# voice-card-controller-1_1-w-thru-hole-xt.net
KiCad netlist of a schematic drawn in EAGLE
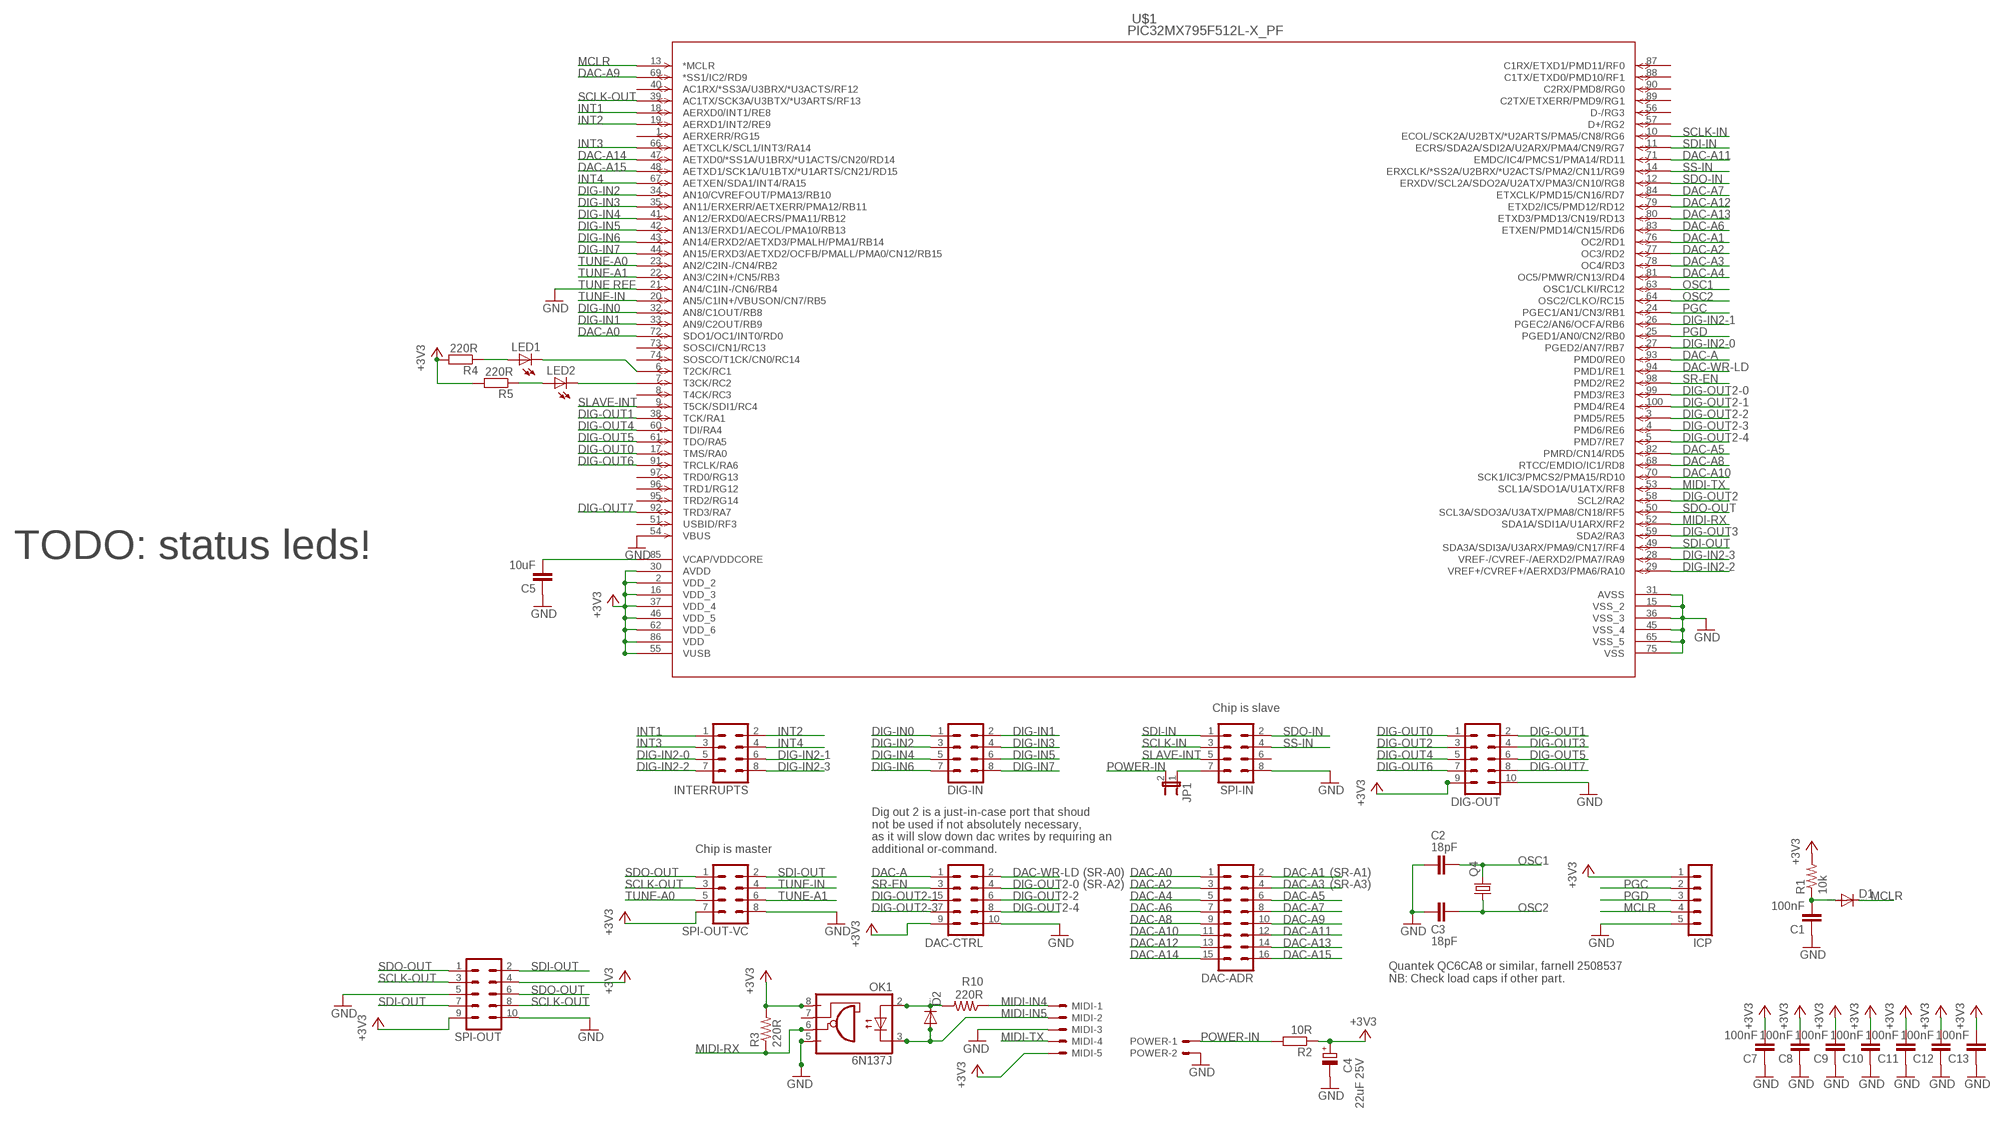
[diagram p0: schematic, sheet 1]

(export (version "E")
  (design (tool "Eeschema 10.0.6"))
  (components
    (comp (ref "C1")
      (value "100nF")
      (footprint "eagle-import:C0603")
      (libsource (lib "eagle-import") (part "C-EUC0603"))
    )
    (comp (ref "C2")
      (value "18pF")
      (footprint "eagle-import:C0603")
      (libsource (lib "eagle-import") (part "C-EUC0603"))
    )
    (comp (ref "C3")
      (value "18pF")
      (footprint "eagle-import:C0603")
      (libsource (lib "eagle-import") (part "C-EUC0603"))
    )
    (comp (ref "C4")
      (value "22uF 25V")
      (footprint "eagle-import:E2,5-5")
      (libsource (lib "eagle-import") (part "CPOL-EUE2.5-5"))
    )
    (comp (ref "C5")
      (value "10uF")
      (footprint "eagle-import:C0805")
      (libsource (lib "eagle-import") (part "C-EUC0805"))
    )
    (comp (ref "C7")
      (value "100nF")
      (footprint "eagle-import:C0603")
      (libsource (lib "eagle-import") (part "C-EUC0603"))
    )
    (comp (ref "C8")
      (value "100nF")
      (footprint "eagle-import:C0603")
      (libsource (lib "eagle-import") (part "C-EUC0603"))
    )
    (comp (ref "C9")
      (value "100nF")
      (footprint "eagle-import:C0603")
      (libsource (lib "eagle-import") (part "C-EUC0603"))
    )
    (comp (ref "C10")
      (value "100nF")
      (footprint "eagle-import:C0603")
      (libsource (lib "eagle-import") (part "C-EUC0603"))
    )
    (comp (ref "C11")
      (value "100nF")
      (footprint "eagle-import:C0603")
      (libsource (lib "eagle-import") (part "C-EUC0603"))
    )
    (comp (ref "C12")
      (value "100nF")
      (footprint "eagle-import:C0603")
      (libsource (lib "eagle-import") (part "C-EUC0603"))
    )
    (comp (ref "C13")
      (value "100nF")
      (footprint "eagle-import:C0603")
      (libsource (lib "eagle-import") (part "C-EUC0603"))
    )
    (comp (ref "D1")
      (value "DIODE-SOD80C")
      (footprint "eagle-import:SOD80C")
      (libsource (lib "eagle-import") (part "DIODE-SOD80C"))
    )
    (comp (ref "D2")
      (value "DIODE-SOD80C")
      (footprint "eagle-import:SOD80C")
      (libsource (lib "eagle-import") (part "DIODE-SOD80C"))
    )
    (comp (ref "DAC-ADR")
      (value "MA08-2J")
      (footprint "eagle-import:MA08-2J")
      (libsource (lib "eagle-import") (part "MA08-2J"))
    )
    (comp (ref "DAC-CTRL")
      (value "MA05-2J")
      (footprint "eagle-import:MA05-2J")
      (libsource (lib "eagle-import") (part "MA05-2J"))
    )
    (comp (ref "DIG-IN")
      (value "MA04-2J")
      (footprint "eagle-import:MA04-2J")
      (libsource (lib "eagle-import") (part "MA04-2J"))
    )
    (comp (ref "DIG-OUT")
      (value "MA05-2J")
      (footprint "eagle-import:MA05-2J")
      (libsource (lib "eagle-import") (part "MA05-2J"))
    )
    (comp (ref "ICP")
      (value "MA05-1")
      (footprint "eagle-import:MA05-1")
      (libsource (lib "eagle-import") (part "MA05-1"))
    )
    (comp (ref "INTERRUPTS")
      (value "MA04-2J")
      (footprint "eagle-import:MA04-2J")
      (libsource (lib "eagle-import") (part "MA04-2J"))
    )
    (comp (ref "JP1")
      (value "JP1E")
      (footprint "eagle-import:JP1")
      (libsource (lib "eagle-import") (part "JP1E"))
    )
    (comp (ref "LED1")
      (value "LEDCHIPLED_0603")
      (footprint "eagle-import:CHIPLED_0603")
      (libsource (lib "eagle-import") (part "LEDCHIPLED_0603"))
    )
    (comp (ref "LED2")
      (value "LEDCHIPLED_0603")
      (footprint "eagle-import:CHIPLED_0603")
      (libsource (lib "eagle-import") (part "LEDCHIPLED_0603"))
    )
    (comp (ref "MIDI")
      (value "22-23-2051")
      (footprint "eagle-import:22-23-2051")
      (fields (field (name "MF") "MOLEX"))
      (libsource (lib "eagle-import") (part "22-23-2051"))
    )
    (comp (ref "OK1")
      (value "6N137J")
      (footprint "eagle-import:DIL08-J")
      (libsource (lib "eagle-import") (part "6N137J"))
    )
    (comp (ref "POWER")
      (value "22-23-2021")
      (footprint "eagle-import:22-23-2021")
      (fields (field (name "MF") "MOLEX"))
      (libsource (lib "eagle-import") (part "22-23-2021"))
    )
    (comp (ref "Q4")
      (value "CRYSTALHC49S")
      (footprint "eagle-import:HC49_S")
      (libsource (lib "eagle-import") (part "CRYSTALHC49S"))
    )
    (comp (ref "R1")
      (value "10k")
      (footprint "eagle-import:R0805")
      (libsource (lib "eagle-import") (part "R-US_R0805"))
    )
    (comp (ref "R2")
      (value "10R")
      (footprint "eagle-import:0207_7")
      (libsource (lib "eagle-import") (part "R-EU_0207/7"))
    )
    (comp (ref "R3")
      (value "220R")
      (footprint "eagle-import:R0805")
      (libsource (lib "eagle-import") (part "R-US_R0805"))
    )
    (comp (ref "R4")
      (value "220R")
      (footprint "eagle-import:R0603")
      (libsource (lib "eagle-import") (part "R-EU_R0603"))
    )
    (comp (ref "R5")
      (value "220R")
      (footprint "eagle-import:R0603")
      (libsource (lib "eagle-import") (part "R-EU_R0603"))
    )
    (comp (ref "R10")
      (value "220R")
      (footprint "eagle-import:R0805")
      (libsource (lib "eagle-import") (part "R-US_R0805"))
    )
    (comp (ref "SPI-IN")
      (value "MA04-2J")
      (footprint "eagle-import:MA04-2J")
      (libsource (lib "eagle-import") (part "MA04-2J"))
    )
    (comp (ref "SPI-OUT")
      (value "MA05-2J")
      (footprint "eagle-import:MA05-2J")
      (libsource (lib "eagle-import") (part "MA05-2J"))
    )
    (comp (ref "SPI-OUT-VC")
      (value "MA04-2J")
      (footprint "eagle-import:MA04-2J")
      (libsource (lib "eagle-import") (part "MA04-2J"))
    )
    (comp (ref "U$1")
      (value "PIC32MX795F512L-X_PF")
      (footprint "eagle-import:TQFP100_14X14MC")
      (libsource (lib "eagle-import") (part "PIC32MX795F512L-X_PF"))
    )
  )
  (nets
    (net (code "1") (name "+3V3") (class "Default")
      (node (ref "C10") (pin "2") (pinfunction "2_2") (pintype "passive"))
      (node (ref "C11") (pin "2") (pinfunction "2_2") (pintype "passive"))
      (node (ref "C12") (pin "2") (pinfunction "2_2") (pintype "passive"))
      (node (ref "C13") (pin "2") (pinfunction "2_2") (pintype "passive"))
      (node (ref "C4") (pin "+") (pinfunction "+_+") (pintype "passive"))
      (node (ref "C7") (pin "2") (pinfunction "2_2") (pintype "passive"))
      (node (ref "C8") (pin "2") (pinfunction "2_2") (pintype "passive"))
      (node (ref "C9") (pin "2") (pinfunction "2_2") (pintype "passive"))
      (node (ref "DAC-CTRL") (pin "9") (pinfunction "9_9") (pintype "passive"))
      (node (ref "DIG-OUT") (pin "9") (pinfunction "9_9") (pintype "passive"))
      (node (ref "ICP") (pin "1") (pinfunction "1_1") (pintype "passive"))
      (node (ref "MIDI") (pin "5") (pinfunction "S_5") (pintype "passive"))
      (node (ref "OK1") (pin "8") (pinfunction "VCC_8") (pintype "passive"))
      (node (ref "R1") (pin "2") (pinfunction "2_2") (pintype "passive"))
      (node (ref "R2") (pin "1") (pinfunction "1_1") (pintype "passive"))
      (node (ref "R3") (pin "2") (pinfunction "2_2") (pintype "passive"))
      (node (ref "R4") (pin "2") (pinfunction "2_2") (pintype "passive"))
      (node (ref "R5") (pin "2") (pinfunction "2_2") (pintype "passive"))
      (node (ref "SPI-OUT") (pin "4") (pinfunction "4_4") (pintype "passive"))
      (node (ref "SPI-OUT") (pin "9") (pinfunction "9_9") (pintype "passive"))
      (node (ref "SPI-OUT-VC") (pin "7") (pinfunction "7_7") (pintype "passive"))
      (node (ref "U$1") (pin "16") (pinfunction "VDD_3_16") (pintype "power_in"))
      (node (ref "U$1") (pin "2") (pinfunction "VDD_2_2") (pintype "power_in"))
      (node (ref "U$1") (pin "30") (pinfunction "AVDD_30") (pintype "power_in"))
      (node (ref "U$1") (pin "37") (pinfunction "VDD_4_37") (pintype "power_in"))
      (node (ref "U$1") (pin "46") (pinfunction "VDD_5_46") (pintype "power_in"))
      (node (ref "U$1") (pin "55") (pinfunction "VUSB_55") (pintype "power_in"))
      (node (ref "U$1") (pin "62") (pinfunction "VDD_6_62") (pintype "power_in"))
      (node (ref "U$1") (pin "86") (pinfunction "VDD_86") (pintype "power_in"))
    )
    (net (code "2") (name "/DAC-A") (class "Default")
      (node (ref "DAC-CTRL") (pin "1") (pinfunction "1_1") (pintype "passive"))
      (node (ref "U$1") (pin "93") (pinfunction "PMD0/RE0_93") (pintype "bidirectional"))
    )
    (net (code "3") (name "/DAC-A0") (class "Default")
      (node (ref "DAC-ADR") (pin "1") (pinfunction "1_1") (pintype "passive"))
      (node (ref "U$1") (pin "72") (pinfunction "SDO1/OC1/INT0/RD0_72") (pintype "bidirectional"))
    )
    (net (code "4") (name "/DAC-A1") (class "Default")
      (node (ref "DAC-ADR") (pin "2") (pinfunction "2_2") (pintype "passive"))
      (node (ref "U$1") (pin "76") (pinfunction "OC2/RD1_76") (pintype "bidirectional"))
    )
    (net (code "5") (name "/DAC-A2") (class "Default")
      (node (ref "DAC-ADR") (pin "3") (pinfunction "3_3") (pintype "passive"))
      (node (ref "U$1") (pin "77") (pinfunction "OC3/RD2_77") (pintype "bidirectional"))
    )
    (net (code "6") (name "/DAC-A3") (class "Default")
      (node (ref "DAC-ADR") (pin "4") (pinfunction "4_4") (pintype "passive"))
      (node (ref "U$1") (pin "78") (pinfunction "OC4/RD3_78") (pintype "bidirectional"))
    )
    (net (code "7") (name "/DAC-A4") (class "Default")
      (node (ref "DAC-ADR") (pin "5") (pinfunction "5_5") (pintype "passive"))
      (node (ref "U$1") (pin "81") (pinfunction "OC5/PMWR/CN13/RD4_81") (pintype "bidirectional"))
    )
    (net (code "8") (name "/DAC-A5") (class "Default")
      (node (ref "DAC-ADR") (pin "6") (pinfunction "6_6") (pintype "passive"))
      (node (ref "U$1") (pin "82") (pinfunction "PMRD/CN14/RD5_82") (pintype "bidirectional"))
    )
    (net (code "9") (name "/DAC-A6") (class "Default")
      (node (ref "DAC-ADR") (pin "7") (pinfunction "7_7") (pintype "passive"))
      (node (ref "U$1") (pin "83") (pinfunction "ETXEN/PMD14/CN15/RD6_83") (pintype "bidirectional"))
    )
    (net (code "10") (name "/DAC-A7") (class "Default")
      (node (ref "DAC-ADR") (pin "8") (pinfunction "8_8") (pintype "passive"))
      (node (ref "U$1") (pin "84") (pinfunction "ETXCLK/PMD15/CN16/RD7_84") (pintype "bidirectional"))
    )
    (net (code "11") (name "/DAC-A8") (class "Default")
      (node (ref "DAC-ADR") (pin "9") (pinfunction "9_9") (pintype "passive"))
      (node (ref "U$1") (pin "68") (pinfunction "RTCC/EMDIO/IC1/RD8_68") (pintype "bidirectional"))
    )
    (net (code "12") (name "/DAC-A9") (class "Default")
      (node (ref "DAC-ADR") (pin "10") (pinfunction "10_10") (pintype "passive"))
      (node (ref "U$1") (pin "69") (pinfunction "*SS1/IC2/RD9_69") (pintype "bidirectional"))
    )
    (net (code "13") (name "/DAC-A10") (class "Default")
      (node (ref "DAC-ADR") (pin "11") (pinfunction "11_11") (pintype "passive"))
      (node (ref "U$1") (pin "70") (pinfunction "SCK1/IC3/PMCS2/PMA15/RD10_70") (pintype "bidirectional"))
    )
    (net (code "14") (name "/DAC-A11") (class "Default")
      (node (ref "DAC-ADR") (pin "12") (pinfunction "12_12") (pintype "passive"))
      (node (ref "U$1") (pin "71") (pinfunction "EMDC/IC4/PMCS1/PMA14/RD11_71") (pintype "bidirectional"))
    )
    (net (code "15") (name "/DAC-A12") (class "Default")
      (node (ref "DAC-ADR") (pin "13") (pinfunction "13_13") (pintype "passive"))
      (node (ref "U$1") (pin "79") (pinfunction "ETXD2/IC5/PMD12/RD12_79") (pintype "bidirectional"))
    )
    (net (code "16") (name "/DAC-A13") (class "Default")
      (node (ref "DAC-ADR") (pin "14") (pinfunction "14_14") (pintype "passive"))
      (node (ref "U$1") (pin "80") (pinfunction "ETXD3/PMD13/CN19/RD13_80") (pintype "bidirectional"))
    )
    (net (code "17") (name "/DAC-A14") (class "Default")
      (node (ref "DAC-ADR") (pin "15") (pinfunction "15_15") (pintype "passive"))
      (node (ref "U$1") (pin "47") (pinfunction "AETXD0/*SS1A/U1BRX/*U1ACTS/CN20/RD14_47") (pintype "bidirectional"))
    )
    (net (code "18") (name "/DAC-A15") (class "Default")
      (node (ref "DAC-ADR") (pin "16") (pinfunction "16_16") (pintype "passive"))
      (node (ref "U$1") (pin "48") (pinfunction "AETXD1/SCK1A/U1BTX/*U1ARTS/CN21/RD15_48") (pintype "bidirectional"))
    )
    (net (code "19") (name "/DAC-WR-LD") (class "Default")
      (node (ref "DAC-CTRL") (pin "2") (pinfunction "2_2") (pintype "passive"))
      (node (ref "U$1") (pin "94") (pinfunction "PMD1/RE1_94") (pintype "bidirectional"))
    )
    (net (code "20") (name "/DIG-IN0") (class "Default")
      (node (ref "DIG-IN") (pin "1") (pinfunction "1_1") (pintype "passive"))
      (node (ref "U$1") (pin "32") (pinfunction "AN8/C1OUT/RB8_32") (pintype "bidirectional"))
    )
    (net (code "21") (name "/DIG-IN1") (class "Default")
      (node (ref "DIG-IN") (pin "2") (pinfunction "2_2") (pintype "passive"))
      (node (ref "U$1") (pin "33") (pinfunction "AN9/C2OUT/RB9_33") (pintype "bidirectional"))
    )
    (net (code "22") (name "/DIG-IN2") (class "Default")
      (node (ref "DIG-IN") (pin "3") (pinfunction "3_3") (pintype "passive"))
      (node (ref "U$1") (pin "34") (pinfunction "AN10/CVREFOUT/PMA13/RB10_34") (pintype "bidirectional"))
    )
    (net (code "23") (name "/DIG-IN2-0") (class "Default")
      (node (ref "INTERRUPTS") (pin "5") (pinfunction "5_5") (pintype "passive"))
      (node (ref "U$1") (pin "27") (pinfunction "PGED2/AN7/RB7_27") (pintype "bidirectional"))
    )
    (net (code "24") (name "/DIG-IN2-1") (class "Default")
      (node (ref "INTERRUPTS") (pin "6") (pinfunction "6_6") (pintype "passive"))
      (node (ref "U$1") (pin "26") (pinfunction "PGEC2/AN6/OCFA/RB6_26") (pintype "bidirectional"))
    )
    (net (code "25") (name "/DIG-IN2-2") (class "Default")
      (node (ref "INTERRUPTS") (pin "7") (pinfunction "7_7") (pintype "passive"))
      (node (ref "U$1") (pin "29") (pinfunction "VREF+/CVREF+/AERXD3/PMA6/RA10_29") (pintype "bidirectional"))
    )
    (net (code "26") (name "/DIG-IN2-3") (class "Default")
      (node (ref "INTERRUPTS") (pin "8") (pinfunction "8_8") (pintype "passive"))
      (node (ref "U$1") (pin "28") (pinfunction "VREF-/CVREF-/AERXD2/PMA7/RA9_28") (pintype "bidirectional"))
    )
    (net (code "27") (name "/DIG-IN3") (class "Default")
      (node (ref "DIG-IN") (pin "4") (pinfunction "4_4") (pintype "passive"))
      (node (ref "U$1") (pin "35") (pinfunction "AN11/ERXERR/AETXERR/PMA12/RB11_35") (pintype "bidirectional"))
    )
    (net (code "28") (name "/DIG-IN4") (class "Default")
      (node (ref "DIG-IN") (pin "5") (pinfunction "5_5") (pintype "passive"))
      (node (ref "U$1") (pin "41") (pinfunction "AN12/ERXD0/AECRS/PMA11/RB12_41") (pintype "bidirectional"))
    )
    (net (code "29") (name "/DIG-IN5") (class "Default")
      (node (ref "DIG-IN") (pin "6") (pinfunction "6_6") (pintype "passive"))
      (node (ref "U$1") (pin "42") (pinfunction "AN13/ERXD1/AECOL/PMA10/RB13_42") (pintype "bidirectional"))
    )
    (net (code "30") (name "/DIG-IN6") (class "Default")
      (node (ref "DIG-IN") (pin "7") (pinfunction "7_7") (pintype "passive"))
      (node (ref "U$1") (pin "43") (pinfunction "AN14/ERXD2/AETXD3/PMALH/PMA1/RB14_43") (pintype "bidirectional"))
    )
    (net (code "31") (name "/DIG-IN7") (class "Default")
      (node (ref "DIG-IN") (pin "8") (pinfunction "8_8") (pintype "passive"))
      (node (ref "U$1") (pin "44") (pinfunction "AN15/ERXD3/AETXD2/OCFB/PMALL/PMA0/CN12/RB15_44") (pintype "bidirectional"))
    )
    (net (code "32") (name "/DIG-OUT0") (class "Default")
      (node (ref "DIG-OUT") (pin "1") (pinfunction "1_1") (pintype "passive"))
      (node (ref "U$1") (pin "17") (pinfunction "TMS/RA0_17") (pintype "bidirectional"))
    )
    (net (code "33") (name "/DIG-OUT1") (class "Default")
      (node (ref "DIG-OUT") (pin "2") (pinfunction "2_2") (pintype "passive"))
      (node (ref "U$1") (pin "38") (pinfunction "TCK/RA1_38") (pintype "bidirectional"))
    )
    (net (code "34") (name "/DIG-OUT2") (class "Default")
      (node (ref "DIG-OUT") (pin "3") (pinfunction "3_3") (pintype "passive"))
      (node (ref "U$1") (pin "58") (pinfunction "SCL2/RA2_58") (pintype "bidirectional"))
    )
    (net (code "35") (name "/DIG-OUT2-0") (class "Default")
      (node (ref "DAC-CTRL") (pin "4") (pinfunction "4_4") (pintype "passive"))
      (node (ref "U$1") (pin "99") (pinfunction "PMD3/RE3_99") (pintype "bidirectional"))
    )
    (net (code "36") (name "/DIG-OUT2-1") (class "Default")
      (node (ref "DAC-CTRL") (pin "5") (pinfunction "5_5") (pintype "passive"))
      (node (ref "U$1") (pin "100") (pinfunction "PMD4/RE4_100") (pintype "bidirectional"))
    )
    (net (code "37") (name "/DIG-OUT2-2") (class "Default")
      (node (ref "DAC-CTRL") (pin "6") (pinfunction "6_6") (pintype "passive"))
      (node (ref "U$1") (pin "3") (pinfunction "PMD5/RE5_3") (pintype "bidirectional"))
    )
    (net (code "38") (name "/DIG-OUT2-3") (class "Default")
      (node (ref "DAC-CTRL") (pin "7") (pinfunction "7_7") (pintype "passive"))
      (node (ref "U$1") (pin "4") (pinfunction "PMD6/RE6_4") (pintype "bidirectional"))
    )
    (net (code "39") (name "/DIG-OUT2-4") (class "Default")
      (node (ref "DAC-CTRL") (pin "8") (pinfunction "8_8") (pintype "passive"))
      (node (ref "U$1") (pin "5") (pinfunction "PMD7/RE7_5") (pintype "bidirectional"))
    )
    (net (code "40") (name "/DIG-OUT3") (class "Default")
      (node (ref "DIG-OUT") (pin "4") (pinfunction "4_4") (pintype "passive"))
      (node (ref "U$1") (pin "59") (pinfunction "SDA2/RA3_59") (pintype "bidirectional"))
    )
    (net (code "41") (name "/DIG-OUT4") (class "Default")
      (node (ref "DIG-OUT") (pin "5") (pinfunction "5_5") (pintype "passive"))
      (node (ref "U$1") (pin "60") (pinfunction "TDI/RA4_60") (pintype "bidirectional"))
    )
    (net (code "42") (name "/DIG-OUT5") (class "Default")
      (node (ref "DIG-OUT") (pin "6") (pinfunction "6_6") (pintype "passive"))
      (node (ref "U$1") (pin "61") (pinfunction "TDO/RA5_61") (pintype "bidirectional"))
    )
    (net (code "43") (name "/DIG-OUT6") (class "Default")
      (node (ref "DIG-OUT") (pin "7") (pinfunction "7_7") (pintype "passive"))
      (node (ref "U$1") (pin "91") (pinfunction "TRCLK/RA6_91") (pintype "bidirectional"))
    )
    (net (code "44") (name "/DIG-OUT7") (class "Default")
      (node (ref "DIG-OUT") (pin "8") (pinfunction "8_8") (pintype "passive"))
      (node (ref "U$1") (pin "92") (pinfunction "TRD3/RA7_92") (pintype "bidirectional"))
    )
    (net (code "45") (name "/INT1") (class "Default")
      (node (ref "INTERRUPTS") (pin "1") (pinfunction "1_1") (pintype "passive"))
      (node (ref "U$1") (pin "18") (pinfunction "AERXD0/INT1/RE8_18") (pintype "bidirectional"))
    )
    (net (code "46") (name "/INT2") (class "Default")
      (node (ref "INTERRUPTS") (pin "2") (pinfunction "2_2") (pintype "passive"))
      (node (ref "U$1") (pin "19") (pinfunction "AERXD1/INT2/RE9_19") (pintype "bidirectional"))
    )
    (net (code "47") (name "/INT3") (class "Default")
      (node (ref "INTERRUPTS") (pin "3") (pinfunction "3_3") (pintype "passive"))
      (node (ref "U$1") (pin "66") (pinfunction "AETXCLK/SCL1/INT3/RA14_66") (pintype "bidirectional"))
    )
    (net (code "48") (name "/INT4") (class "Default")
      (node (ref "INTERRUPTS") (pin "4") (pinfunction "4_4") (pintype "passive"))
      (node (ref "U$1") (pin "67") (pinfunction "AETXEN/SDA1/INT4/RA15_67") (pintype "bidirectional"))
    )
    (net (code "49") (name "/MCLR") (class "Default")
      (node (ref "D1") (pin "C") (pinfunction "C_C") (pintype "passive"))
      (node (ref "ICP") (pin "4") (pinfunction "4_4") (pintype "passive"))
      (node (ref "U$1") (pin "13") (pinfunction "*MCLR_13") (pintype "input"))
    )
    (net (code "50") (name "/MIDI-IN4") (class "Default")
      (node (ref "MIDI") (pin "1") (pinfunction "S_1") (pintype "passive"))
      (node (ref "R10") (pin "1") (pinfunction "1_1") (pintype "passive"))
    )
    (net (code "51") (name "/MIDI-IN5") (class "Default")
      (node (ref "D2") (pin "A") (pinfunction "A_A") (pintype "passive"))
      (node (ref "MIDI") (pin "2") (pinfunction "S_2") (pintype "passive"))
      (node (ref "OK1") (pin "3") (pinfunction "C_3") (pintype "passive"))
    )
    (net (code "52") (name "/MIDI-RX") (class "Default")
      (node (ref "OK1") (pin "6") (pinfunction "VO_6") (pintype "passive"))
      (node (ref "R3") (pin "1") (pinfunction "1_1") (pintype "passive"))
      (node (ref "U$1") (pin "52") (pinfunction "SDA1A/SDI1A/U1ARX/RF2_52") (pintype "bidirectional"))
    )
    (net (code "53") (name "/MIDI-TX") (class "Default")
      (node (ref "MIDI") (pin "4") (pinfunction "S_4") (pintype "passive"))
      (node (ref "U$1") (pin "53") (pinfunction "SCL1A/SDO1A/U1ATX/RF8_53") (pintype "bidirectional"))
    )
    (net (code "54") (name "/OSC1") (class "Default")
      (node (ref "C2") (pin "1") (pinfunction "1_1") (pintype "passive"))
      (node (ref "Q4") (pin "2") (pinfunction "2_2") (pintype "passive"))
      (node (ref "U$1") (pin "63") (pinfunction "OSC1/CLKI/RC12_63") (pintype "bidirectional"))
    )
    (net (code "55") (name "/OSC2") (class "Default")
      (node (ref "C3") (pin "1") (pinfunction "1_1") (pintype "passive"))
      (node (ref "Q4") (pin "1") (pinfunction "1_1") (pintype "passive"))
      (node (ref "U$1") (pin "64") (pinfunction "OSC2/CLKO/RC15_64") (pintype "bidirectional"))
    )
    (net (code "56") (name "/PGC") (class "Default")
      (node (ref "ICP") (pin "2") (pinfunction "2_2") (pintype "passive"))
      (node (ref "U$1") (pin "24") (pinfunction "PGEC1/AN1/CN3/RB1_24") (pintype "bidirectional"))
    )
    (net (code "57") (name "/PGD") (class "Default")
      (node (ref "ICP") (pin "3") (pinfunction "3_3") (pintype "passive"))
      (node (ref "U$1") (pin "25") (pinfunction "PGED1/AN0/CN2/RB0_25") (pintype "bidirectional"))
    )
    (net (code "58") (name "/POWER-IN") (class "Default")
      (node (ref "JP1") (pin "2") (pinfunction "2_2") (pintype "passive"))
      (node (ref "POWER") (pin "1") (pinfunction "S_1") (pintype "passive"))
      (node (ref "R2") (pin "2") (pinfunction "2_2") (pintype "passive"))
    )
    (net (code "59") (name "/SCLK-IN") (class "Default")
      (node (ref "SPI-IN") (pin "3") (pinfunction "3_3") (pintype "passive"))
      (node (ref "U$1") (pin "10") (pinfunction "ECOL/SCK2A/U2BTX/*U2ARTS/PMA5/CN8/RG6_10") (pintype "bidirectional"))
    )
    (net (code "60") (name "/SCLK-OUT") (class "Default")
      (node (ref "SPI-OUT") (pin "3") (pinfunction "3_3") (pintype "passive"))
      (node (ref "SPI-OUT") (pin "8") (pinfunction "8_8") (pintype "passive"))
      (node (ref "SPI-OUT-VC") (pin "3") (pinfunction "3_3") (pintype "passive"))
      (node (ref "U$1") (pin "39") (pinfunction "AC1TX/SCK3A/U3BTX/*U3ARTS/RF13_39") (pintype "bidirectional"))
    )
    (net (code "61") (name "/SDI-IN") (class "Default")
      (node (ref "SPI-IN") (pin "1") (pinfunction "1_1") (pintype "passive"))
      (node (ref "U$1") (pin "11") (pinfunction "ECRS/SDA2A/SDI2A/U2ARX/PMA4/CN9/RG7_11") (pintype "bidirectional"))
    )
    (net (code "62") (name "/SDI-OUT") (class "Default")
      (node (ref "SPI-OUT") (pin "2") (pinfunction "2_2") (pintype "passive"))
      (node (ref "SPI-OUT") (pin "7") (pinfunction "7_7") (pintype "passive"))
      (node (ref "SPI-OUT-VC") (pin "2") (pinfunction "2_2") (pintype "passive"))
      (node (ref "U$1") (pin "49") (pinfunction "SDA3A/SDI3A/U3ARX/PMA9/CN17/RF4_49") (pintype "bidirectional"))
    )
    (net (code "63") (name "/SDO-IN") (class "Default")
      (node (ref "SPI-IN") (pin "2") (pinfunction "2_2") (pintype "passive"))
      (node (ref "U$1") (pin "12") (pinfunction "ERXDV/SCL2A/SDO2A/U2ATX/PMA3/CN10/RG8_12") (pintype "bidirectional"))
    )
    (net (code "64") (name "/SDO-OUT") (class "Default")
      (node (ref "SPI-OUT") (pin "1") (pinfunction "1_1") (pintype "passive"))
      (node (ref "SPI-OUT") (pin "6") (pinfunction "6_6") (pintype "passive"))
      (node (ref "SPI-OUT-VC") (pin "1") (pinfunction "1_1") (pintype "passive"))
      (node (ref "U$1") (pin "50") (pinfunction "SCL3A/SDO3A/U3ATX/PMA8/CN18/RF5_50") (pintype "bidirectional"))
    )
    (net (code "65") (name "/SLAVE-INT") (class "Default")
      (node (ref "SPI-IN") (pin "5") (pinfunction "5_5") (pintype "passive"))
      (node (ref "U$1") (pin "9") (pinfunction "T5CK/SDI1/RC4_9") (pintype "bidirectional"))
    )
    (net (code "66") (name "/SR-EN") (class "Default")
      (node (ref "DAC-CTRL") (pin "3") (pinfunction "3_3") (pintype "passive"))
      (node (ref "U$1") (pin "98") (pinfunction "PMD2/RE2_98") (pintype "bidirectional"))
    )
    (net (code "67") (name "/SS-IN") (class "Default")
      (node (ref "SPI-IN") (pin "4") (pinfunction "4_4") (pintype "passive"))
      (node (ref "U$1") (pin "14") (pinfunction "ERXCLK/*SS2A/U2BRX/*U2ACTS/PMA2/CN11/RG9_14") (pintype "bidirectional"))
    )
    (net (code "68") (name "/TUNE-A0") (class "Default")
      (node (ref "SPI-OUT-VC") (pin "5") (pinfunction "5_5") (pintype "passive"))
      (node (ref "U$1") (pin "23") (pinfunction "AN2/C2IN-/CN4/RB2_23") (pintype "bidirectional"))
    )
    (net (code "69") (name "/TUNE-A1") (class "Default")
      (node (ref "SPI-OUT-VC") (pin "6") (pinfunction "6_6") (pintype "passive"))
      (node (ref "U$1") (pin "22") (pinfunction "AN3/C2IN+/CN5/RB3_22") (pintype "bidirectional"))
    )
    (net (code "70") (name "/TUNE-IN") (class "Default")
      (node (ref "SPI-OUT-VC") (pin "4") (pinfunction "4_4") (pintype "passive"))
      (node (ref "U$1") (pin "20") (pinfunction "AN5/C1IN+/VBUSON/CN7/RB5_20") (pintype "bidirectional"))
    )
    (net (code "71") (name "GND") (class "Default")
      (node (ref "C1") (pin "1") (pinfunction "1_1") (pintype "passive"))
      (node (ref "C10") (pin "1") (pinfunction "1_1") (pintype "passive"))
      (node (ref "C11") (pin "1") (pinfunction "1_1") (pintype "passive"))
      (node (ref "C12") (pin "1") (pinfunction "1_1") (pintype "passive"))
      (node (ref "C13") (pin "1") (pinfunction "1_1") (pintype "passive"))
      (node (ref "C2") (pin "2") (pinfunction "2_2") (pintype "passive"))
      (node (ref "C3") (pin "2") (pinfunction "2_2") (pintype "passive"))
      (node (ref "C4") (pin "-") (pinfunction "-_-") (pintype "passive"))
      (node (ref "C5") (pin "1") (pinfunction "1_1") (pintype "passive"))
      (node (ref "C7") (pin "1") (pinfunction "1_1") (pintype "passive"))
      (node (ref "C8") (pin "1") (pinfunction "1_1") (pintype "passive"))
      (node (ref "C9") (pin "1") (pinfunction "1_1") (pintype "passive"))
      (node (ref "DAC-CTRL") (pin "10") (pinfunction "10_10") (pintype "passive"))
      (node (ref "DIG-OUT") (pin "10") (pinfunction "10_10") (pintype "passive"))
      (node (ref "ICP") (pin "5") (pinfunction "5_5") (pintype "passive"))
      (node (ref "MIDI") (pin "3") (pinfunction "S_3") (pintype "passive"))
      (node (ref "OK1") (pin "5") (pinfunction "GND_5") (pintype "passive"))
      (node (ref "POWER") (pin "2") (pinfunction "S_2") (pintype "passive"))
      (node (ref "SPI-IN") (pin "8") (pinfunction "8_8") (pintype "passive"))
      (node (ref "SPI-OUT") (pin "10") (pinfunction "10_10") (pintype "passive"))
      (node (ref "SPI-OUT") (pin "5") (pinfunction "5_5") (pintype "passive"))
      (node (ref "SPI-OUT-VC") (pin "8") (pinfunction "8_8") (pintype "passive"))
      (node (ref "U$1") (pin "15") (pinfunction "VSS_2_15") (pintype "power_in"))
      (node (ref "U$1") (pin "21") (pinfunction "AN4/C1IN-/CN6/RB4_21") (pintype "bidirectional"))
      (node (ref "U$1") (pin "31") (pinfunction "AVSS_31") (pintype "power_in"))
      (node (ref "U$1") (pin "36") (pinfunction "VSS_3_36") (pintype "power_in"))
      (node (ref "U$1") (pin "45") (pinfunction "VSS_4_45") (pintype "power_in"))
      (node (ref "U$1") (pin "54") (pinfunction "VBUS_54") (pintype "input"))
      (node (ref "U$1") (pin "65") (pinfunction "VSS_5_65") (pintype "power_in"))
      (node (ref "U$1") (pin "75") (pinfunction "VSS_75") (pintype "power_in"))
    )
    (net (code "72") (name "Net-(C1-Pad2)") (class "Default")
      (node (ref "C1") (pin "2") (pinfunction "2_2") (pintype "passive"))
      (node (ref "D1") (pin "A") (pinfunction "A_A") (pintype "passive"))
      (node (ref "R1") (pin "1") (pinfunction "1_1") (pintype "passive"))
    )
    (net (code "73") (name "Net-(JP1-Pad1)") (class "Default")
      (node (ref "JP1") (pin "1") (pinfunction "1_1") (pintype "passive"))
      (node (ref "SPI-IN") (pin "7") (pinfunction "7_7") (pintype "passive"))
    )
    (net (code "74") (name "Net-(LED1-PadA)") (class "Default")
      (node (ref "LED1") (pin "A") (pinfunction "A_A") (pintype "passive"))
      (node (ref "R4") (pin "1") (pinfunction "1_1") (pintype "passive"))
    )
    (net (code "75") (name "Net-(LED2-PadA)") (class "Default")
      (node (ref "LED2") (pin "A") (pinfunction "A_A") (pintype "passive"))
      (node (ref "R5") (pin "1") (pinfunction "1_1") (pintype "passive"))
    )
    (net (code "76") (name "Net-(OK1-A)") (class "Default")
      (node (ref "D2") (pin "C") (pinfunction "C_C") (pintype "passive"))
      (node (ref "OK1") (pin "2") (pinfunction "A_2") (pintype "passive"))
      (node (ref "R10") (pin "2") (pinfunction "2_2") (pintype "passive"))
    )
    (net (code "77") (name "Net-(U$1-T2CK{slash}RC1)") (class "Default")
      (node (ref "LED1") (pin "C") (pinfunction "C_C") (pintype "passive"))
      (node (ref "U$1") (pin "6") (pinfunction "T2CK/RC1_6") (pintype "bidirectional"))
    )
    (net (code "78") (name "Net-(U$1-T3CK{slash}RC2)") (class "Default")
      (node (ref "LED2") (pin "C") (pinfunction "C_C") (pintype "passive"))
      (node (ref "U$1") (pin "7") (pinfunction "T3CK/RC2_7") (pintype "bidirectional"))
    )
    (net (code "79") (name "Net-(U$1-VCAP{slash}VDDCORE)") (class "Default")
      (node (ref "C5") (pin "2") (pinfunction "2_2") (pintype "passive"))
      (node (ref "U$1") (pin "85") (pinfunction "VCAP/VDDCORE_85") (pintype "power_in"))
    )
    (net (code "80") (name "unconnected-(OK1-VE-Pad7)") (class "Default")
      (node (ref "OK1") (pin "7") (pinfunction "VE_7") (pintype "passive"))
    )
    (net (code "81") (name "unconnected-(SPI-IN-Pad6)") (class "Default")
      (node (ref "SPI-IN") (pin "6") (pinfunction "6_6") (pintype "passive"))
    )
    (net (code "82") (name "unconnected-(U$1-AC1RX{slash}*SS3A{slash}U3BRX{slash}*U3ACTS{slash}RF12-Pad40)") (class "Default")
      (node (ref "U$1") (pin "40") (pinfunction "AC1RX/*SS3A/U3BRX/*U3ACTS/RF12_40") (pintype "bidirectional"))
    )
    (net (code "83") (name "unconnected-(U$1-AERXERR{slash}RG15-Pad1)") (class "Default")
      (node (ref "U$1") (pin "1") (pinfunction "AERXERR/RG15_1") (pintype "bidirectional"))
    )
    (net (code "84") (name "unconnected-(U$1-C1RX{slash}ETXD1{slash}PMD11{slash}RF0-Pad87)") (class "Default")
      (node (ref "U$1") (pin "87") (pinfunction "C1RX/ETXD1/PMD11/RF0_87") (pintype "bidirectional"))
    )
    (net (code "85") (name "unconnected-(U$1-C1TX{slash}ETXD0{slash}PMD10{slash}RF1-Pad88)") (class "Default")
      (node (ref "U$1") (pin "88") (pinfunction "C1TX/ETXD0/PMD10/RF1_88") (pintype "bidirectional"))
    )
    (net (code "86") (name "unconnected-(U$1-C2RX{slash}PMD8{slash}RG0-Pad90)") (class "Default")
      (node (ref "U$1") (pin "90") (pinfunction "C2RX/PMD8/RG0_90") (pintype "bidirectional"))
    )
    (net (code "87") (name "unconnected-(U$1-C2TX{slash}ETXERR{slash}PMD9{slash}RG1-Pad89)") (class "Default")
      (node (ref "U$1") (pin "89") (pinfunction "C2TX/ETXERR/PMD9/RG1_89") (pintype "bidirectional"))
    )
    (net (code "88") (name "unconnected-(U$1-D+{slash}RG2-Pad57)") (class "Default")
      (node (ref "U$1") (pin "57") (pinfunction "D+/RG2_57") (pintype "bidirectional"))
    )
    (net (code "89") (name "unconnected-(U$1-D-{slash}RG3-Pad56)") (class "Default")
      (node (ref "U$1") (pin "56") (pinfunction "D-/RG3_56") (pintype "bidirectional"))
    )
    (net (code "90") (name "unconnected-(U$1-SOSCI{slash}CN1{slash}RC13-Pad73)") (class "Default")
      (node (ref "U$1") (pin "73") (pinfunction "SOSCI/CN1/RC13_73") (pintype "bidirectional"))
    )
    (net (code "91") (name "unconnected-(U$1-SOSCO{slash}T1CK{slash}CN0{slash}RC14-Pad74)") (class "Default")
      (node (ref "U$1") (pin "74") (pinfunction "SOSCO/T1CK/CN0/RC14_74") (pintype "bidirectional"))
    )
    (net (code "92") (name "unconnected-(U$1-T4CK{slash}RC3-Pad8)") (class "Default")
      (node (ref "U$1") (pin "8") (pinfunction "T4CK/RC3_8") (pintype "bidirectional"))
    )
    (net (code "93") (name "unconnected-(U$1-TRD0{slash}RG13-Pad97)") (class "Default")
      (node (ref "U$1") (pin "97") (pinfunction "TRD0/RG13_97") (pintype "bidirectional"))
    )
    (net (code "94") (name "unconnected-(U$1-TRD1{slash}RG12-Pad96)") (class "Default")
      (node (ref "U$1") (pin "96") (pinfunction "TRD1/RG12_96") (pintype "bidirectional"))
    )
    (net (code "95") (name "unconnected-(U$1-TRD2{slash}RG14-Pad95)") (class "Default")
      (node (ref "U$1") (pin "95") (pinfunction "TRD2/RG14_95") (pintype "bidirectional"))
    )
    (net (code "96") (name "unconnected-(U$1-USBID{slash}RF3-Pad51)") (class "Default")
      (node (ref "U$1") (pin "51") (pinfunction "USBID/RF3_51") (pintype "bidirectional"))
    )
  )
)
